# dcdc_mc34063_down_5to-5.net
KiCad netlist of a schematic drawn in EAGLE
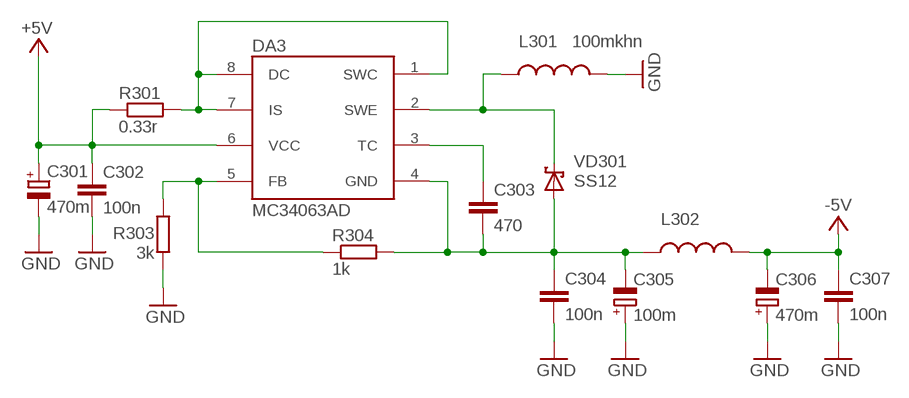
[diagram p0: schematic, sheet 1]

(export (version "E")
  (design (tool "Eeschema 10.0.6"))
  (components
    (comp (ref "C301")
      (value "470m")
      (footprint "eagle-import:E3,5-8")
      (libsource (lib "eagle-import") (part "CPOL-EUE3.5-8"))
    )
    (comp (ref "C302")
      (value "100n")
      (footprint "eagle-import:C0805")
      (libsource (lib "eagle-import") (part "C-EUC0805"))
    )
    (comp (ref "C303")
      (value "470")
      (footprint "eagle-import:C0805")
      (libsource (lib "eagle-import") (part "C-EUC0805"))
    )
    (comp (ref "C304")
      (value "100n")
      (footprint "eagle-import:C0805")
      (libsource (lib "eagle-import") (part "C-EUC0805"))
    )
    (comp (ref "C305")
      (value "100m")
      (footprint "eagle-import:E2,5-5")
      (libsource (lib "eagle-import") (part "CPOL-EUE2.5-5"))
    )
    (comp (ref "C306")
      (value "470m")
      (footprint "eagle-import:E3,5-8")
      (libsource (lib "eagle-import") (part "CPOL-EUE3.5-8"))
    )
    (comp (ref "C307")
      (value "100n")
      (footprint "eagle-import:C0805")
      (libsource (lib "eagle-import") (part "C-EUC0805"))
    )
    (comp (ref "DA3")
      (value "MC34063AD")
      (footprint "eagle-import:SOIC8")
      (libsource (lib "eagle-import") (part "MC34063AD"))
    )
    (comp (ref "L301")
      (value "100mkhn")
      (footprint "eagle-import:TFI0305")
      (libsource (lib "eagle-import") (part "L-USTFI0305"))
    )
    (comp (ref "L302")
      (value "L-US0204/7")
      (footprint "eagle-import:0204_7")
      (libsource (lib "eagle-import") (part "L-US0204/7"))
    )
    (comp (ref "R301")
      (value "0.33r")
      (footprint "eagle-import:M1206")
      (libsource (lib "eagle-import") (part "R-EU_M1206"))
    )
    (comp (ref "R303")
      (value "3k")
      (footprint "eagle-import:M0805")
      (libsource (lib "eagle-import") (part "R-EU_M0805"))
    )
    (comp (ref "R304")
      (value "1k")
      (footprint "eagle-import:M0805")
      (libsource (lib "eagle-import") (part "R-EU_M0805"))
    )
    (comp (ref "VD301")
      (value "SS12")
      (footprint "eagle-import:SMB")
      (libsource (lib "eagle-import") (part "SCHOTTKY-DIODESMD"))
    )
  )
  (nets
    (net (code "1") (name "+5V") (class "Default")
      (node (ref "C301") (pin "+") (pinfunction "+_+") (pintype "passive"))
      (node (ref "C302") (pin "1") (pinfunction "1_1") (pintype "passive"))
      (node (ref "DA3") (pin "6") (pinfunction "VCC_6") (pintype "passive"))
      (node (ref "R301") (pin "1") (pinfunction "1_1") (pintype "passive"))
    )
    (net (code "2") (name "-5V") (class "Default")
      (node (ref "C306") (pin "-") (pinfunction "-_-") (pintype "passive"))
      (node (ref "C307") (pin "1") (pinfunction "1_1") (pintype "passive"))
      (node (ref "L302") (pin "2") (pinfunction "2_2") (pintype "passive"))
    )
    (net (code "3") (name "GND") (class "Default")
      (node (ref "C301") (pin "-") (pinfunction "-_-") (pintype "passive"))
      (node (ref "C302") (pin "2") (pinfunction "2_2") (pintype "passive"))
      (node (ref "C304") (pin "2") (pinfunction "2_2") (pintype "passive"))
      (node (ref "C305") (pin "+") (pinfunction "+_+") (pintype "passive"))
      (node (ref "C306") (pin "+") (pinfunction "+_+") (pintype "passive"))
      (node (ref "C307") (pin "2") (pinfunction "2_2") (pintype "passive"))
      (node (ref "L301") (pin "2") (pinfunction "2_2") (pintype "passive"))
      (node (ref "R303") (pin "1") (pinfunction "1_1") (pintype "passive"))
    )
    (net (code "4") (name "Net-(DA3-DC)") (class "Default")
      (node (ref "DA3") (pin "1") (pinfunction "SWC_1") (pintype "passive"))
      (node (ref "DA3") (pin "7") (pinfunction "IS_7") (pintype "passive"))
      (node (ref "DA3") (pin "8") (pinfunction "DC_8") (pintype "passive"))
      (node (ref "R301") (pin "2") (pinfunction "2_2") (pintype "passive"))
    )
    (net (code "5") (name "Net-(DA3-FB)") (class "Default")
      (node (ref "DA3") (pin "5") (pinfunction "FB_5") (pintype "passive"))
      (node (ref "R303") (pin "2") (pinfunction "2_2") (pintype "passive"))
      (node (ref "R304") (pin "1") (pinfunction "1_1") (pintype "passive"))
    )
    (net (code "6") (name "Net-(DA3-GND)") (class "Default")
      (node (ref "C303") (pin "2") (pinfunction "2_2") (pintype "passive"))
      (node (ref "C304") (pin "1") (pinfunction "1_1") (pintype "passive"))
      (node (ref "C305") (pin "-") (pinfunction "-_-") (pintype "passive"))
      (node (ref "DA3") (pin "4") (pinfunction "GND_4") (pintype "passive"))
      (node (ref "L302") (pin "1") (pinfunction "1_1") (pintype "passive"))
      (node (ref "R304") (pin "2") (pinfunction "2_2") (pintype "passive"))
      (node (ref "VD301") (pin "A") (pinfunction "A_A") (pintype "passive"))
    )
    (net (code "7") (name "Net-(DA3-SWE)") (class "Default")
      (node (ref "DA3") (pin "2") (pinfunction "SWE_2") (pintype "passive"))
      (node (ref "L301") (pin "1") (pinfunction "1_1") (pintype "passive"))
      (node (ref "VD301") (pin "C") (pinfunction "C_C") (pintype "passive"))
    )
    (net (code "8") (name "Net-(DA3-TC)") (class "Default")
      (node (ref "C303") (pin "1") (pinfunction "1_1") (pintype "passive"))
      (node (ref "DA3") (pin "3") (pinfunction "TC_3") (pintype "passive"))
    )
  )
)
